# 2019_Dashboard.net
KiCad netlist of a schematic drawn in EAGLE
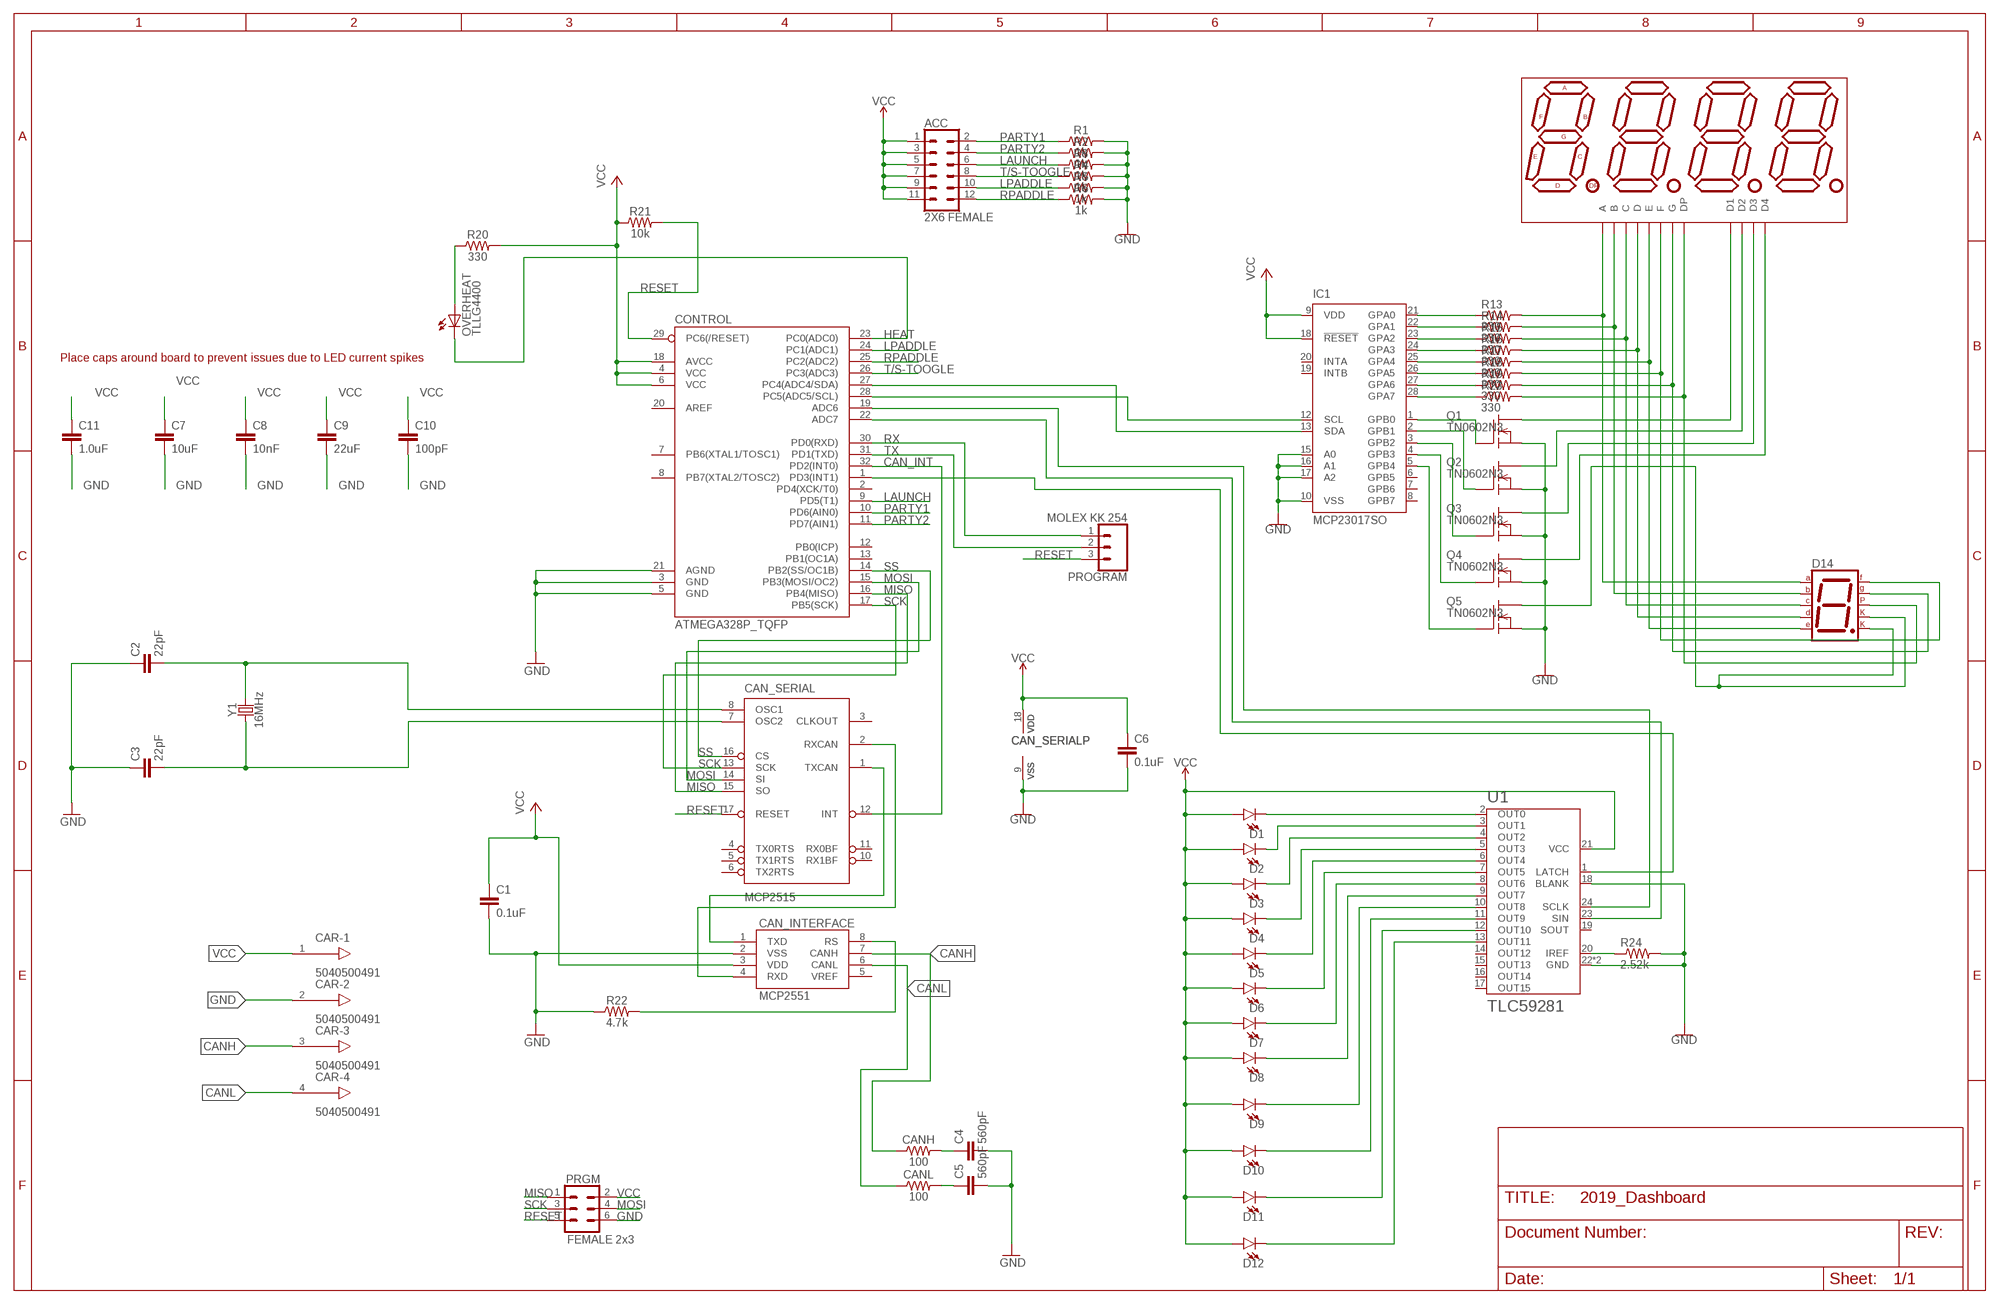
[diagram p0: schematic, sheet 1]

(export (version "E")
  (design (tool "Eeschema 10.0.6"))
  (components
    (comp (ref "ACC")
      (value "2X6 FEMALE")
      (footprint "eagle-import:2X6")
      (libsource (lib "eagle-import") (part "CONN_06X2PTH_FEMALE"))
    )
    (comp (ref "C1")
      (value "0.1uF")
      (footprint "eagle-import:0603")
      (libsource (lib "eagle-import") (part "0.1UF-0603-25V-(+80/-20%)"))
    )
    (comp (ref "C2")
      (value "22pF")
      (footprint "eagle-import:0603")
      (libsource (lib "eagle-import") (part "22PF-0603-50V-5%"))
    )
    (comp (ref "C3")
      (value "22pF")
      (footprint "eagle-import:0603")
      (libsource (lib "eagle-import") (part "22PF-0603-50V-5%"))
    )
    (comp (ref "C4")
      (value "560pF")
      (footprint "eagle-import:0603")
      (libsource (lib "eagle-import") (part "560PF-0603-50V-5%"))
    )
    (comp (ref "C5")
      (value "560pF")
      (footprint "eagle-import:0603")
      (libsource (lib "eagle-import") (part "560PF-0603-50V-5%"))
    )
    (comp (ref "C6")
      (value "0.1uF")
      (footprint "eagle-import:0402")
      (libsource (lib "eagle-import") (part "0.1UF-0402-16V-10%"))
    )
    (comp (ref "C7")
      (value "10uF")
      (footprint "eagle-import:0805")
      (libsource (lib "eagle-import") (part "10UF-0805-10V-10%"))
    )
    (comp (ref "C8")
      (value "10nF")
      (footprint "eagle-import:0603")
      (libsource (lib "eagle-import") (part "10NF-0603-50V-10%"))
    )
    (comp (ref "C9")
      (value "22uF")
      (footprint "eagle-import:0805")
      (libsource (lib "eagle-import") (part "22UF-0805-6.3V-20%"))
    )
    (comp (ref "C10")
      (value "100pF")
      (footprint "eagle-import:0603")
      (libsource (lib "eagle-import") (part "100PF-0603-50V-5%"))
    )
    (comp (ref "C11")
      (value "1.0uF")
      (footprint "eagle-import:0805")
      (libsource (lib "eagle-import") (part "1.0UF-0805-25V-(+80/-20%)"))
    )
    (comp (ref "CANH")
      (value "100")
      (footprint "eagle-import:0603")
      (libsource (lib "eagle-import") (part "100OHM-0603-1/4W-5%"))
    )
    (comp (ref "CANL")
      (value "100")
      (footprint "eagle-import:0603")
      (libsource (lib "eagle-import") (part "100OHM-0603-1/4W-5%"))
    )
    (comp (ref "CAN_INTERFACE")
      (value "MCP2551")
      (footprint "eagle-import:SO08")
      (libsource (lib "eagle-import") (part "MCP2551"))
    )
    (comp (ref "CAN_SERIAL")
      (value "MCP2515")
      (footprint "eagle-import:SO18W")
      (libsource (lib "eagle-import") (part "MCP2515(MCP2510)SO"))
    )
    (comp (ref "CAR")
      (value "5040500491")
      (footprint "eagle-import:PICOLOCK505050-0491")
      (fields (field (name "MANUFACTURER") "Molex Inc"))
      (libsource (lib "eagle-import") (part "5040500491"))
    )
    (comp (ref "CONTROL")
      (value "ATMEGA328P_TQFP")
      (footprint "eagle-import:TQFP32-08")
      (libsource (lib "eagle-import") (part "ATMEGA328P_TQFP"))
    )
    (comp (ref "D1")
      (value "LED5MM")
      (footprint "eagle-import:LED_5MM")
      (libsource (lib "eagle-import") (part "LED5MM"))
    )
    (comp (ref "D2")
      (value "LED5MM")
      (footprint "eagle-import:LED_5MM")
      (libsource (lib "eagle-import") (part "LED5MM"))
    )
    (comp (ref "D3")
      (value "LED5MM")
      (footprint "eagle-import:LED_5MM")
      (libsource (lib "eagle-import") (part "LED5MM"))
    )
    (comp (ref "D4")
      (value "LED5MM")
      (footprint "eagle-import:LED_5MM")
      (libsource (lib "eagle-import") (part "LED5MM"))
    )
    (comp (ref "D5")
      (value "LED5MM")
      (footprint "eagle-import:LED_5MM")
      (libsource (lib "eagle-import") (part "LED5MM"))
    )
    (comp (ref "D6")
      (value "LED5MM")
      (footprint "eagle-import:LED_5MM")
      (libsource (lib "eagle-import") (part "LED5MM"))
    )
    (comp (ref "D7")
      (value "LED5MM")
      (footprint "eagle-import:LED_5MM")
      (libsource (lib "eagle-import") (part "LED5MM"))
    )
    (comp (ref "D8")
      (value "LED5MM")
      (footprint "eagle-import:LED_5MM")
      (libsource (lib "eagle-import") (part "LED5MM"))
    )
    (comp (ref "D9")
      (value "LED5MM")
      (footprint "eagle-import:LED_5MM")
      (libsource (lib "eagle-import") (part "LED5MM"))
    )
    (comp (ref "D10")
      (value "LED5MM")
      (footprint "eagle-import:LED_5MM")
      (libsource (lib "eagle-import") (part "LED5MM"))
    )
    (comp (ref "D11")
      (value "LED5MM")
      (footprint "eagle-import:LED_5MM")
      (libsource (lib "eagle-import") (part "LED5MM"))
    )
    (comp (ref "D12")
      (value "LED5MM")
      (footprint "eagle-import:LED_5MM")
      (libsource (lib "eagle-import") (part "LED5MM"))
    )
    (comp (ref "D14")
      (value "7SEG-CK")
      (footprint "eagle-import:7SEG-13")
      (libsource (lib "eagle-import") (part "7SEG-CK"))
    )
    (comp (ref "DISP1")
      (value "ATA8041ARBJ")
      (footprint "eagle-import:7-SEGMENT-4DIGIT-20MM")
      (libsource (lib "eagle-import") (part "7-SEGMENT-4DIGIT-20MM-RED"))
    )
    (comp (ref "IC1")
      (value "MCP23017SO")
      (footprint "eagle-import:SO28W")
      (libsource (lib "eagle-import") (part "MCP23017SO"))
    )
    (comp (ref "OVERHEAT")
      (value "TLLG4400")
      (footprint "eagle-import:LED3MM")
      (fields (field (name "MF") "VISHAY SEMICONDUCTOR"))
      (libsource (lib "eagle-import") (part "TLLG4400"))
    )
    (comp (ref "PRGM")
      (value "FEMALE 2x3")
      (footprint "eagle-import:2X3")
      (libsource (lib "eagle-import") (part "CONN_03X2FEMALE"))
    )
    (comp (ref "PROGRAM")
      (value "MOLEX KK 254")
      (footprint "eagle-import:1X03")
      (libsource (lib "eagle-import") (part "CONN_03"))
    )
    (comp (ref "Q1")
      (value "TN0602N3")
      (footprint "eagle-import:TO-92")
      (libsource (lib "eagle-import") (part "TN0602N3"))
    )
    (comp (ref "Q2")
      (value "TN0602N3")
      (footprint "eagle-import:TO-92")
      (libsource (lib "eagle-import") (part "TN0602N3"))
    )
    (comp (ref "Q3")
      (value "TN0602N3")
      (footprint "eagle-import:TO-92")
      (libsource (lib "eagle-import") (part "TN0602N3"))
    )
    (comp (ref "Q4")
      (value "TN0602N3")
      (footprint "eagle-import:TO-92")
      (libsource (lib "eagle-import") (part "TN0602N3"))
    )
    (comp (ref "Q5")
      (value "TN0602N3")
      (footprint "eagle-import:TO-92")
      (libsource (lib "eagle-import") (part "TN0602N3"))
    )
    (comp (ref "R1")
      (value "1k")
      (footprint "eagle-import:0603")
      (libsource (lib "eagle-import") (part "1KOHM-0603-1/10W-1%"))
    )
    (comp (ref "R2")
      (value "1k")
      (footprint "eagle-import:0603")
      (libsource (lib "eagle-import") (part "1KOHM-0603-1/10W-1%"))
    )
    (comp (ref "R3")
      (value "1k")
      (footprint "eagle-import:0603")
      (libsource (lib "eagle-import") (part "1KOHM-0603-1/10W-1%"))
    )
    (comp (ref "R4")
      (value "1k")
      (footprint "eagle-import:0603")
      (libsource (lib "eagle-import") (part "1KOHM-0603-1/10W-1%"))
    )
    (comp (ref "R5")
      (value "1k")
      (footprint "eagle-import:0603")
      (libsource (lib "eagle-import") (part "1KOHM-0603-1/10W-1%"))
    )
    (comp (ref "R6")
      (value "1k")
      (footprint "eagle-import:0603")
      (libsource (lib "eagle-import") (part "1KOHM-0603-1/10W-1%"))
    )
    (comp (ref "R13")
      (value "330")
      (footprint "eagle-import:R0603")
      (libsource (lib "eagle-import") (part "R-US_R0603"))
    )
    (comp (ref "R14")
      (value "330")
      (footprint "eagle-import:R0603")
      (libsource (lib "eagle-import") (part "R-US_R0603"))
    )
    (comp (ref "R15")
      (value "330")
      (footprint "eagle-import:R0603")
      (libsource (lib "eagle-import") (part "R-US_R0603"))
    )
    (comp (ref "R16")
      (value "330")
      (footprint "eagle-import:R0603")
      (libsource (lib "eagle-import") (part "R-US_R0603"))
    )
    (comp (ref "R17")
      (value "330")
      (footprint "eagle-import:R0603")
      (libsource (lib "eagle-import") (part "R-US_R0603"))
    )
    (comp (ref "R18")
      (value "330")
      (footprint "eagle-import:R0603")
      (libsource (lib "eagle-import") (part "R-US_R0603"))
    )
    (comp (ref "R19")
      (value "330")
      (footprint "eagle-import:R0603")
      (libsource (lib "eagle-import") (part "R-US_R0603"))
    )
    (comp (ref "R20")
      (value "330")
      (footprint "eagle-import:0603")
      (libsource (lib "eagle-import") (part "330OHM-0603-1/10W-1%"))
    )
    (comp (ref "R21")
      (value "10k")
      (footprint "eagle-import:0603")
      (libsource (lib "eagle-import") (part "10KOHM-0603-1/10W-1%"))
    )
    (comp (ref "R22")
      (value "4.7k")
      (footprint "eagle-import:0603")
      (libsource (lib "eagle-import") (part "4.7KOHM-0603-1/10W-1%"))
    )
    (comp (ref "R23")
      (value "330")
      (footprint "eagle-import:R0603")
      (libsource (lib "eagle-import") (part "R-US_R0603"))
    )
    (comp (ref "R24")
      (value "2.52k")
      (footprint "eagle-import:R0603")
      (libsource (lib "eagle-import") (part "R-US_R0603"))
    )
    (comp (ref "U1")
      (value "TLC59281")
      (footprint "eagle-import:QFN-24")
      (fields (field (name "MF") "Texas Instruments"))
      (libsource (lib "eagle-import") (part "TLC59281"))
    )
    (comp (ref "Y1")
      (value "16MHz")
      (footprint "eagle-import:HC49US")
      (libsource (lib "eagle-import") (part "CRYSTAL-16MHZPTH-HC49US"))
    )
  )
  (nets
    (net (code "1") (name "/CAN_INT") (class "Default")
      (node (ref "CAN_SERIAL") (pin "12") (pinfunction "INT_12") (pintype "output"))
      (node (ref "CONTROL") (pin "32") (pinfunction "PD2(INT0)_32") (pintype "bidirectional"))
    )
    (net (code "2") (name "/HEAT") (class "Default")
      (node (ref "CONTROL") (pin "23") (pinfunction "PC0(ADC0)_23") (pintype "bidirectional"))
      (node (ref "OVERHEAT") (pin "K") (pinfunction "C_K") (pintype "passive"))
    )
    (net (code "3") (name "/LAUNCH") (class "Default")
      (node (ref "ACC") (pin "6") (pinfunction "6_6") (pintype "passive"))
      (node (ref "CONTROL") (pin "9") (pinfunction "PD5(T1)_9") (pintype "bidirectional"))
      (node (ref "R3") (pin "1") (pinfunction "1_1") (pintype "passive"))
    )
    (net (code "4") (name "/LPADDLE") (class "Default")
      (node (ref "ACC") (pin "10") (pinfunction "10_10") (pintype "passive"))
      (node (ref "CONTROL") (pin "24") (pinfunction "PC1(ADC1)_24") (pintype "bidirectional"))
      (node (ref "R5") (pin "1") (pinfunction "1_1") (pintype "passive"))
    )
    (net (code "5") (name "/MISO") (class "Default")
      (node (ref "CAN_SERIAL") (pin "15") (pinfunction "SO_15") (pintype "output"))
      (node (ref "CONTROL") (pin "16") (pinfunction "PB4(MISO)_16") (pintype "bidirectional"))
      (node (ref "PRGM") (pin "1") (pinfunction "1_1") (pintype "bidirectional"))
    )
    (net (code "6") (name "/MOSI") (class "Default")
      (node (ref "CAN_SERIAL") (pin "14") (pinfunction "SI_14") (pintype "input"))
      (node (ref "CONTROL") (pin "15") (pinfunction "PB3(MOSI/OC2)_15") (pintype "bidirectional"))
      (node (ref "PRGM") (pin "4") (pinfunction "4_4") (pintype "bidirectional"))
    )
    (net (code "7") (name "/PARTY1") (class "Default")
      (node (ref "ACC") (pin "2") (pinfunction "2_2") (pintype "passive"))
      (node (ref "CONTROL") (pin "10") (pinfunction "PD6(AIN0)_10") (pintype "bidirectional"))
      (node (ref "R1") (pin "1") (pinfunction "1_1") (pintype "passive"))
    )
    (net (code "8") (name "/PARTY2") (class "Default")
      (node (ref "ACC") (pin "4") (pinfunction "4_4") (pintype "passive"))
      (node (ref "CONTROL") (pin "11") (pinfunction "PD7(AIN1)_11") (pintype "bidirectional"))
      (node (ref "R2") (pin "1") (pinfunction "1_1") (pintype "passive"))
    )
    (net (code "9") (name "/RESET") (class "Default")
      (node (ref "CAN_SERIAL") (pin "17") (pinfunction "RESET_17") (pintype "input"))
      (node (ref "CONTROL") (pin "29") (pinfunction "PC6(/RESET)_29") (pintype "bidirectional"))
      (node (ref "PRGM") (pin "5") (pinfunction "5_5") (pintype "bidirectional"))
      (node (ref "PROGRAM") (pin "3") (pinfunction "3_3") (pintype "passive"))
      (node (ref "R21") (pin "2") (pinfunction "2_2") (pintype "passive"))
    )
    (net (code "10") (name "/RPADDLE") (class "Default")
      (node (ref "ACC") (pin "12") (pinfunction "12_12") (pintype "passive"))
      (node (ref "CONTROL") (pin "25") (pinfunction "PC2(ADC2)_25") (pintype "bidirectional"))
      (node (ref "R6") (pin "1") (pinfunction "1_1") (pintype "passive"))
    )
    (net (code "11") (name "/RX") (class "Default")
      (node (ref "CONTROL") (pin "30") (pinfunction "PD0(RXD)_30") (pintype "bidirectional"))
      (node (ref "PROGRAM") (pin "1") (pinfunction "1_1") (pintype "passive"))
    )
    (net (code "12") (name "/SCK") (class "Default")
      (node (ref "CAN_SERIAL") (pin "13") (pinfunction "SCK_13") (pintype "input"))
      (node (ref "CONTROL") (pin "17") (pinfunction "PB5(SCK)_17") (pintype "bidirectional"))
      (node (ref "PRGM") (pin "3") (pinfunction "3_3") (pintype "bidirectional"))
    )
    (net (code "13") (name "/SS") (class "Default")
      (node (ref "CAN_SERIAL") (pin "16") (pinfunction "CS_16") (pintype "input"))
      (node (ref "CONTROL") (pin "14") (pinfunction "PB2(SS/OC1B)_14") (pintype "bidirectional"))
    )
    (net (code "14") (name "/TX") (class "Default")
      (node (ref "CONTROL") (pin "31") (pinfunction "PD1(TXD)_31") (pintype "bidirectional"))
      (node (ref "PROGRAM") (pin "2") (pinfunction "2_2") (pintype "passive"))
    )
    (net (code "15") (name "/T{slash}S-TOOGLE") (class "Default")
      (node (ref "ACC") (pin "8") (pinfunction "8_8") (pintype "passive"))
      (node (ref "CONTROL") (pin "26") (pinfunction "PC3(ADC3)_26") (pintype "bidirectional"))
      (node (ref "R4") (pin "1") (pinfunction "1_1") (pintype "passive"))
    )
    (net (code "16") (name "CANH") (class "Default")
      (node (ref "CANH") (pin "1") (pinfunction "1_1") (pintype "passive"))
      (node (ref "CAN_INTERFACE") (pin "7") (pinfunction "CANH_7") (pintype "bidirectional"))
      (node (ref "CAR") (pin "3") (pinfunction "P$1_3") (pintype "bidirectional"))
    )
    (net (code "17") (name "CANL") (class "Default")
      (node (ref "CANL") (pin "1") (pinfunction "1_1") (pintype "passive"))
      (node (ref "CAN_INTERFACE") (pin "6") (pinfunction "CANL_6") (pintype "bidirectional"))
      (node (ref "CAR") (pin "4") (pinfunction "P$1_4") (pintype "bidirectional"))
    )
    (net (code "18") (name "GND") (class "Default")
      (node (ref "C1") (pin "2") (pinfunction "2_2") (pintype "passive"))
      (node (ref "C10") (pin "2") (pinfunction "2_2") (pintype "passive"))
      (node (ref "C11") (pin "2") (pinfunction "2_2") (pintype "passive"))
      (node (ref "C2") (pin "1") (pinfunction "1_1") (pintype "passive"))
      (node (ref "C3") (pin "1") (pinfunction "1_1") (pintype "passive"))
      (node (ref "C4") (pin "2") (pinfunction "2_2") (pintype "passive"))
      (node (ref "C5") (pin "2") (pinfunction "2_2") (pintype "passive"))
      (node (ref "C6") (pin "2") (pinfunction "2_2") (pintype "passive"))
      (node (ref "C7") (pin "2") (pinfunction "2_2") (pintype "passive"))
      (node (ref "C8") (pin "2") (pinfunction "2_2") (pintype "passive"))
      (node (ref "C9") (pin "2") (pinfunction "2_2") (pintype "passive"))
      (node (ref "CAN_INTERFACE") (pin "2") (pinfunction "VSS_2") (pintype "bidirectional"))
      (node (ref "CAN_SERIAL") (pin "9") (pinfunction "VSS_9") (pintype "power_in"))
      (node (ref "CAR") (pin "2") (pinfunction "P$1_2") (pintype "bidirectional"))
      (node (ref "CONTROL") (pin "21") (pinfunction "AGND_21") (pintype "bidirectional"))
      (node (ref "CONTROL") (pin "3") (pinfunction "GND_3") (pintype "bidirectional"))
      (node (ref "CONTROL") (pin "5") (pinfunction "GND_5") (pintype "bidirectional"))
      (node (ref "IC1") (pin "10") (pinfunction "VSS_10") (pintype "power_in"))
      (node (ref "IC1") (pin "15") (pinfunction "A0_15") (pintype "input"))
      (node (ref "IC1") (pin "16") (pinfunction "A1_16") (pintype "input"))
      (node (ref "IC1") (pin "17") (pinfunction "A2_17") (pintype "input"))
      (node (ref "PRGM") (pin "6") (pinfunction "6_6") (pintype "bidirectional"))
      (node (ref "Q1") (pin "1") (pinfunction "S_1") (pintype "passive"))
      (node (ref "Q2") (pin "1") (pinfunction "S_1") (pintype "passive"))
      (node (ref "Q3") (pin "1") (pinfunction "S_1") (pintype "passive"))
      (node (ref "Q4") (pin "1") (pinfunction "S_1") (pintype "passive"))
      (node (ref "Q5") (pin "1") (pinfunction "S_1") (pintype "passive"))
      (node (ref "R1") (pin "2") (pinfunction "2_2") (pintype "passive"))
      (node (ref "R2") (pin "2") (pinfunction "2_2") (pintype "passive"))
      (node (ref "R22") (pin "1") (pinfunction "1_1") (pintype "passive"))
      (node (ref "R24") (pin "2") (pinfunction "2_2") (pintype "passive"))
      (node (ref "R3") (pin "2") (pinfunction "2_2") (pintype "passive"))
      (node (ref "R4") (pin "2") (pinfunction "2_2") (pintype "passive"))
      (node (ref "R5") (pin "2") (pinfunction "2_2") (pintype "passive"))
      (node (ref "R6") (pin "2") (pinfunction "2_2") (pintype "passive"))
      (node (ref "U1") (pin "18") (pinfunction "BLANK_18") (pintype "bidirectional"))
      (node (ref "U1") (pin "22") (pinfunction "GND_22") (pintype "bidirectional"))
      (node (ref "U1") (pin "EP") (pinfunction "GND_EP") (pintype "bidirectional"))
    )
    (net (code "19") (name "Net-(C4-Pad1)") (class "Default")
      (node (ref "C4") (pin "1") (pinfunction "1_1") (pintype "passive"))
      (node (ref "CANH") (pin "2") (pinfunction "2_2") (pintype "passive"))
    )
    (net (code "20") (name "Net-(C5-Pad1)") (class "Default")
      (node (ref "C5") (pin "1") (pinfunction "1_1") (pintype "passive"))
      (node (ref "CANL") (pin "2") (pinfunction "2_2") (pintype "passive"))
    )
    (net (code "21") (name "Net-(CAN_INTERFACE-RS)") (class "Default")
      (node (ref "CAN_INTERFACE") (pin "8") (pinfunction "RS_8") (pintype "bidirectional"))
      (node (ref "R22") (pin "2") (pinfunction "2_2") (pintype "passive"))
    )
    (net (code "22") (name "Net-(CAN_INTERFACE-RXD)") (class "Default")
      (node (ref "CAN_INTERFACE") (pin "4") (pinfunction "RXD_4") (pintype "bidirectional"))
      (node (ref "CAN_SERIAL") (pin "2") (pinfunction "RXCAN_2") (pintype "input"))
    )
    (net (code "23") (name "Net-(CAN_INTERFACE-TXD)") (class "Default")
      (node (ref "CAN_INTERFACE") (pin "1") (pinfunction "TXD_1") (pintype "bidirectional"))
      (node (ref "CAN_SERIAL") (pin "1") (pinfunction "TXCAN_1") (pintype "output"))
    )
    (net (code "24") (name "Net-(CAN_SERIALA-OSC1)") (class "Default")
      (node (ref "C2") (pin "2") (pinfunction "2_2") (pintype "passive"))
      (node (ref "CAN_SERIAL") (pin "8") (pinfunction "OSC1_8") (pintype "input"))
      (node (ref "Y1") (pin "2") (pinfunction "2_2") (pintype "passive"))
    )
    (net (code "25") (name "Net-(CAN_SERIALA-OSC2)") (class "Default")
      (node (ref "C3") (pin "2") (pinfunction "2_2") (pintype "passive"))
      (node (ref "CAN_SERIAL") (pin "7") (pinfunction "OSC2_7") (pintype "output"))
      (node (ref "Y1") (pin "1") (pinfunction "1_1") (pintype "passive"))
    )
    (net (code "26") (name "Net-(CONTROL-ADC6)") (class "Default")
      (node (ref "CONTROL") (pin "19") (pinfunction "ADC6_19") (pintype "bidirectional"))
      (node (ref "U1") (pin "24") (pinfunction "SCLK_24") (pintype "bidirectional"))
    )
    (net (code "27") (name "Net-(CONTROL-ADC7)") (class "Default")
      (node (ref "CONTROL") (pin "22") (pinfunction "ADC7_22") (pintype "bidirectional"))
      (node (ref "U1") (pin "23") (pinfunction "SIN_23") (pintype "bidirectional"))
    )
    (net (code "28") (name "Net-(CONTROL-PC4(ADC4{slash}SDA))") (class "Default")
      (node (ref "CONTROL") (pin "27") (pinfunction "PC4(ADC4/SDA)_27") (pintype "bidirectional"))
      (node (ref "IC1") (pin "13") (pinfunction "SDA_13") (pintype "bidirectional"))
    )
    (net (code "29") (name "Net-(CONTROL-PC5(ADC5{slash}SCL))") (class "Default")
      (node (ref "CONTROL") (pin "28") (pinfunction "PC5(ADC5/SCL)_28") (pintype "bidirectional"))
      (node (ref "IC1") (pin "12") (pinfunction "SCL_12") (pintype "input"))
    )
    (net (code "30") (name "Net-(CONTROL-PD3(INT1))") (class "Default")
      (node (ref "CONTROL") (pin "1") (pinfunction "PD3(INT1)_1") (pintype "bidirectional"))
      (node (ref "U1") (pin "1") (pinfunction "LATCH_1") (pintype "bidirectional"))
    )
    (net (code "31") (name "Net-(D1-C)") (class "Default")
      (node (ref "D1") (pin "K") (pinfunction "C_K") (pintype "passive"))
      (node (ref "U1") (pin "2") (pinfunction "OUT0_2") (pintype "bidirectional"))
    )
    (net (code "32") (name "Net-(D2-C)") (class "Default")
      (node (ref "D2") (pin "K") (pinfunction "C_K") (pintype "passive"))
      (node (ref "U1") (pin "3") (pinfunction "OUT1_3") (pintype "bidirectional"))
    )
    (net (code "33") (name "Net-(D3-C)") (class "Default")
      (node (ref "D3") (pin "K") (pinfunction "C_K") (pintype "passive"))
      (node (ref "U1") (pin "4") (pinfunction "OUT2_4") (pintype "bidirectional"))
    )
    (net (code "34") (name "Net-(D4-C)") (class "Default")
      (node (ref "D4") (pin "K") (pinfunction "C_K") (pintype "passive"))
      (node (ref "U1") (pin "5") (pinfunction "OUT3_5") (pintype "bidirectional"))
    )
    (net (code "35") (name "Net-(D5-C)") (class "Default")
      (node (ref "D5") (pin "K") (pinfunction "C_K") (pintype "passive"))
      (node (ref "U1") (pin "6") (pinfunction "OUT4_6") (pintype "bidirectional"))
    )
    (net (code "36") (name "Net-(D6-C)") (class "Default")
      (node (ref "D6") (pin "K") (pinfunction "C_K") (pintype "passive"))
      (node (ref "U1") (pin "7") (pinfunction "OUT5_7") (pintype "bidirectional"))
    )
    (net (code "37") (name "Net-(D7-C)") (class "Default")
      (node (ref "D7") (pin "K") (pinfunction "C_K") (pintype "passive"))
      (node (ref "U1") (pin "8") (pinfunction "OUT6_8") (pintype "bidirectional"))
    )
    (net (code "38") (name "Net-(D8-C)") (class "Default")
      (node (ref "D8") (pin "K") (pinfunction "C_K") (pintype "passive"))
      (node (ref "U1") (pin "9") (pinfunction "OUT7_9") (pintype "bidirectional"))
    )
    (net (code "39") (name "Net-(D9-C)") (class "Default")
      (node (ref "D9") (pin "K") (pinfunction "C_K") (pintype "passive"))
      (node (ref "U1") (pin "10") (pinfunction "OUT8_10") (pintype "bidirectional"))
    )
    (net (code "40") (name "Net-(D10-C)") (class "Default")
      (node (ref "D10") (pin "K") (pinfunction "C_K") (pintype "passive"))
      (node (ref "U1") (pin "11") (pinfunction "OUT9_11") (pintype "bidirectional"))
    )
    (net (code "41") (name "Net-(D11-C)") (class "Default")
      (node (ref "D11") (pin "K") (pinfunction "C_K") (pintype "passive"))
      (node (ref "U1") (pin "12") (pinfunction "OUT10_12") (pintype "bidirectional"))
    )
    (net (code "42") (name "Net-(D12-C)") (class "Default")
      (node (ref "D12") (pin "K") (pinfunction "C_K") (pintype "passive"))
      (node (ref "U1") (pin "13") (pinfunction "OUT11_13") (pintype "bidirectional"))
    )
    (net (code "43") (name "Net-(D14-A)") (class "Default")
      (node (ref "D14") (pin "7") (pinfunction "A_7") (pintype "passive"))
      (node (ref "DISP1") (pin "11") (pinfunction "A_11") (pintype "bidirectional"))
      (node (ref "R13") (pin "2") (pinfunction "2_2") (pintype "passive"))
    )
    (net (code "44") (name "Net-(D14-B)") (class "Default")
      (node (ref "D14") (pin "6") (pinfunction "B_6") (pintype "passive"))
      (node (ref "DISP1") (pin "7") (pinfunction "B_7") (pintype "bidirectional"))
      (node (ref "R14") (pin "2") (pinfunction "2_2") (pintype "passive"))
    )
    (net (code "45") (name "Net-(D14-C)") (class "Default")
      (node (ref "D14") (pin "4") (pinfunction "C_4") (pintype "passive"))
      (node (ref "DISP1") (pin "4") (pinfunction "C_4") (pintype "bidirectional"))
      (node (ref "R15") (pin "2") (pinfunction "2_2") (pintype "passive"))
    )
    (net (code "46") (name "Net-(D14-CK1)") (class "Default")
      (node (ref "D14") (pin "3") (pinfunction "CK1_3") (pintype "passive"))
      (node (ref "D14") (pin "8") (pinfunction "CK2_8") (pintype "passive"))
      (node (ref "Q5") (pin "3") (pinfunction "D_3") (pintype "passive"))
    )
    (net (code "47") (name "Net-(D14-D)") (class "Default")
      (node (ref "D14") (pin "2") (pinfunction "D_2") (pintype "passive"))
      (node (ref "DISP1") (pin "2") (pinfunction "D_2") (pintype "bidirectional"))
      (node (ref "R16") (pin "2") (pinfunction "2_2") (pintype "passive"))
    )
    (net (code "48") (name "Net-(D14-DP)") (class "Default")
      (node (ref "D14") (pin "5") (pinfunction "DP_5") (pintype "passive"))
      (node (ref "DISP1") (pin "3") (pinfunction "DP_3") (pintype "bidirectional"))
      (node (ref "R23") (pin "2") (pinfunction "2_2") (pintype "passive"))
    )
    (net (code "49") (name "Net-(D14-E)") (class "Default")
      (node (ref "D14") (pin "1") (pinfunction "E_1") (pintype "passive"))
      (node (ref "DISP1") (pin "1") (pinfunction "E_1") (pintype "bidirectional"))
      (node (ref "R17") (pin "2") (pinfunction "2_2") (pintype "passive"))
    )
    (net (code "50") (name "Net-(D14-F)") (class "Default")
      (node (ref "D14") (pin "9") (pinfunction "F_9") (pintype "passive"))
      (node (ref "DISP1") (pin "10") (pinfunction "F_10") (pintype "bidirectional"))
      (node (ref "R18") (pin "2") (pinfunction "2_2") (pintype "passive"))
    )
    (net (code "51") (name "Net-(D14-G)") (class "Default")
      (node (ref "D14") (pin "10") (pinfunction "G_10") (pintype "passive"))
      (node (ref "DISP1") (pin "5") (pinfunction "G_5") (pintype "bidirectional"))
      (node (ref "R19") (pin "2") (pinfunction "2_2") (pintype "passive"))
    )
    (net (code "52") (name "Net-(DISP1-D1)") (class "Default")
      (node (ref "DISP1") (pin "12") (pinfunction "D1_12") (pintype "bidirectional"))
      (node (ref "Q1") (pin "3") (pinfunction "D_3") (pintype "passive"))
    )
    (net (code "53") (name "Net-(DISP1-D2)") (class "Default")
      (node (ref "DISP1") (pin "9") (pinfunction "D2_9") (pintype "bidirectional"))
      (node (ref "Q2") (pin "3") (pinfunction "D_3") (pintype "passive"))
    )
    (net (code "54") (name "Net-(DISP1-D3)") (class "Default")
      (node (ref "DISP1") (pin "8") (pinfunction "D3_8") (pintype "bidirectional"))
      (node (ref "Q3") (pin "3") (pinfunction "D_3") (pintype "passive"))
    )
    (net (code "55") (name "Net-(DISP1-D4)") (class "Default")
      (node (ref "DISP1") (pin "6") (pinfunction "D4_6") (pintype "bidirectional"))
      (node (ref "Q4") (pin "3") (pinfunction "D_3") (pintype "passive"))
    )
    (net (code "56") (name "Net-(IC1-GPA0)") (class "Default")
      (node (ref "IC1") (pin "21") (pinfunction "GPA0_21") (pintype "bidirectional"))
      (node (ref "R13") (pin "1") (pinfunction "1_1") (pintype "passive"))
    )
    (net (code "57") (name "Net-(IC1-GPA1)") (class "Default")
      (node (ref "IC1") (pin "22") (pinfunction "GPA1_22") (pintype "bidirectional"))
      (node (ref "R14") (pin "1") (pinfunction "1_1") (pintype "passive"))
    )
    (net (code "58") (name "Net-(IC1-GPA2)") (class "Default")
      (node (ref "IC1") (pin "23") (pinfunction "GPA2_23") (pintype "bidirectional"))
      (node (ref "R15") (pin "1") (pinfunction "1_1") (pintype "passive"))
    )
    (net (code "59") (name "Net-(IC1-GPA3)") (class "Default")
      (node (ref "IC1") (pin "24") (pinfunction "GPA3_24") (pintype "bidirectional"))
      (node (ref "R16") (pin "1") (pinfunction "1_1") (pintype "passive"))
    )
    (net (code "60") (name "Net-(IC1-GPA4)") (class "Default")
      (node (ref "IC1") (pin "25") (pinfunction "GPA4_25") (pintype "bidirectional"))
      (node (ref "R17") (pin "1") (pinfunction "1_1") (pintype "passive"))
    )
    (net (code "61") (name "Net-(IC1-GPA5)") (class "Default")
      (node (ref "IC1") (pin "26") (pinfunction "GPA5_26") (pintype "bidirectional"))
      (node (ref "R18") (pin "1") (pinfunction "1_1") (pintype "passive"))
    )
    (net (code "62") (name "Net-(IC1-GPA6)") (class "Default")
      (node (ref "IC1") (pin "27") (pinfunction "GPA6_27") (pintype "bidirectional"))
      (node (ref "R19") (pin "1") (pinfunction "1_1") (pintype "passive"))
    )
    (net (code "63") (name "Net-(IC1-GPA7)") (class "Default")
      (node (ref "IC1") (pin "28") (pinfunction "GPA7_28") (pintype "bidirectional"))
      (node (ref "R23") (pin "1") (pinfunction "1_1") (pintype "passive"))
    )
    (net (code "64") (name "Net-(IC1-GPB0)") (class "Default")
      (node (ref "IC1") (pin "1") (pinfunction "GPB0_1") (pintype "bidirectional"))
      (node (ref "Q1") (pin "2") (pinfunction "G_2") (pintype "passive"))
    )
    (net (code "65") (name "Net-(IC1-GPB1)") (class "Default")
      (node (ref "IC1") (pin "2") (pinfunction "GPB1_2") (pintype "bidirectional"))
      (node (ref "Q2") (pin "2") (pinfunction "G_2") (pintype "passive"))
    )
    (net (code "66") (name "Net-(IC1-GPB2)") (class "Default")
      (node (ref "IC1") (pin "3") (pinfunction "GPB2_3") (pintype "bidirectional"))
      (node (ref "Q3") (pin "2") (pinfunction "G_2") (pintype "passive"))
    )
    (net (code "67") (name "Net-(IC1-GPB3)") (class "Default")
      (node (ref "IC1") (pin "4") (pinfunction "GPB3_4") (pintype "bidirectional"))
      (node (ref "Q4") (pin "2") (pinfunction "G_2") (pintype "passive"))
    )
    (net (code "68") (name "Net-(IC1-GPB4)") (class "Default")
      (node (ref "IC1") (pin "5") (pinfunction "GPB4_5") (pintype "bidirectional"))
      (node (ref "Q5") (pin "2") (pinfunction "G_2") (pintype "passive"))
    )
    (net (code "69") (name "Net-(OVERHEAT-PadA)") (class "Default")
      (node (ref "OVERHEAT") (pin "A") (pinfunction "A_A") (pintype "passive"))
      (node (ref "R20") (pin "1") (pinfunction "1_1") (pintype "passive"))
    )
    (net (code "70") (name "Net-(U1-IREF)") (class "Default")
      (node (ref "R24") (pin "1") (pinfunction "1_1") (pintype "passive"))
      (node (ref "U1") (pin "20") (pinfunction "IREF_20") (pintype "bidirectional"))
    )
    (net (code "71") (name "VCC") (class "Default")
      (node (ref "ACC") (pin "1") (pinfunction "1_1") (pintype "passive"))
      (node (ref "ACC") (pin "11") (pinfunction "11_11") (pintype "passive"))
      (node (ref "ACC") (pin "3") (pinfunction "3_3") (pintype "passive"))
      (node (ref "ACC") (pin "5") (pinfunction "5_5") (pintype "passive"))
      (node (ref "ACC") (pin "7") (pinfunction "7_7") (pintype "passive"))
      (node (ref "ACC") (pin "9") (pinfunction "9_9") (pintype "passive"))
      (node (ref "C1") (pin "1") (pinfunction "1_1") (pintype "passive"))
      (node (ref "C10") (pin "1") (pinfunction "1_1") (pintype "passive"))
      (node (ref "C11") (pin "1") (pinfunction "1_1") (pintype "passive"))
      (node (ref "C6") (pin "1") (pinfunction "1_1") (pintype "passive"))
      (node (ref "C7") (pin "1") (pinfunction "1_1") (pintype "passive"))
      (node (ref "C8") (pin "1") (pinfunction "1_1") (pintype "passive"))
      (node (ref "C9") (pin "1") (pinfunction "1_1") (pintype "passive"))
      (node (ref "CAN_INTERFACE") (pin "3") (pinfunction "VDD_3") (pintype "bidirectional"))
      (node (ref "CAN_SERIAL") (pin "18") (pinfunction "VDD_18") (pintype "power_in"))
      (node (ref "CAR") (pin "1") (pinfunction "P$1_1") (pintype "bidirectional"))
      (node (ref "CONTROL") (pin "18") (pinfunction "AVCC_18") (pintype "bidirectional"))
      (node (ref "CONTROL") (pin "4") (pinfunction "VCC_4") (pintype "bidirectional"))
      (node (ref "CONTROL") (pin "6") (pinfunction "VCC_6") (pintype "bidirectional"))
      (node (ref "D1") (pin "A") (pinfunction "A_A") (pintype "passive"))
      (node (ref "D10") (pin "A") (pinfunction "A_A") (pintype "passive"))
      (node (ref "D11") (pin "A") (pinfunction "A_A") (pintype "passive"))
      (node (ref "D12") (pin "A") (pinfunction "A_A") (pintype "passive"))
      (node (ref "D2") (pin "A") (pinfunction "A_A") (pintype "passive"))
      (node (ref "D3") (pin "A") (pinfunction "A_A") (pintype "passive"))
      (node (ref "D4") (pin "A") (pinfunction "A_A") (pintype "passive"))
      (node (ref "D5") (pin "A") (pinfunction "A_A") (pintype "passive"))
      (node (ref "D6") (pin "A") (pinfunction "A_A") (pintype "passive"))
      (node (ref "D7") (pin "A") (pinfunction "A_A") (pintype "passive"))
      (node (ref "D8") (pin "A") (pinfunction "A_A") (pintype "passive"))
      (node (ref "D9") (pin "A") (pinfunction "A_A") (pintype "passive"))
      (node (ref "IC1") (pin "18") (pinfunction "~{RESET}_18") (pintype "input"))
      (node (ref "IC1") (pin "9") (pinfunction "VDD_9") (pintype "power_in"))
      (node (ref "PRGM") (pin "2") (pinfunction "2_2") (pintype "bidirectional"))
      (node (ref "R20") (pin "2") (pinfunction "2_2") (pintype "passive"))
      (node (ref "R21") (pin "1") (pinfunction "1_1") (pintype "passive"))
      (node (ref "U1") (pin "21") (pinfunction "VCC_21") (pintype "bidirectional"))
    )
    (net (code "72") (name "unconnected-(CAN_INTERFACE-VREF-Pad5)") (class "Default")
      (node (ref "CAN_INTERFACE") (pin "5") (pinfunction "VREF_5") (pintype "bidirectional"))
    )
    (net (code "73") (name "unconnected-(CAN_SERIALA-CLKOUT-Pad3)") (class "Default")
      (node (ref "CAN_SERIAL") (pin "3") (pinfunction "CLKOUT_3") (pintype "output"))
    )
    (net (code "74") (name "unconnected-(CAN_SERIALA-RX0BF-Pad11)") (class "Default")
      (node (ref "CAN_SERIAL") (pin "11") (pinfunction "RX0BF_11") (pintype "output"))
    )
    (net (code "75") (name "unconnected-(CAN_SERIALA-RX1BF-Pad10)") (class "Default")
      (node (ref "CAN_SERIAL") (pin "10") (pinfunction "RX1BF_10") (pintype "output"))
    )
    (net (code "76") (name "unconnected-(CAN_SERIALA-TX0RTS-Pad4)") (class "Default")
      (node (ref "CAN_SERIAL") (pin "4") (pinfunction "TX0RTS_4") (pintype "input"))
    )
    (net (code "77") (name "unconnected-(CAN_SERIALA-TX1RTS-Pad5)") (class "Default")
      (node (ref "CAN_SERIAL") (pin "5") (pinfunction "TX1RTS_5") (pintype "input"))
    )
    (net (code "78") (name "unconnected-(CAN_SERIALA-TX2RTS-Pad6)") (class "Default")
      (node (ref "CAN_SERIAL") (pin "6") (pinfunction "TX2RTS_6") (pintype "input"))
    )
    (net (code "79") (name "unconnected-(CONTROL-AREF-Pad20)") (class "Default")
      (node (ref "CONTROL") (pin "20") (pinfunction "AREF_20") (pintype "bidirectional"))
    )
    (net (code "80") (name "unconnected-(CONTROL-PB0(ICP)-Pad12)") (class "Default")
      (node (ref "CONTROL") (pin "12") (pinfunction "PB0(ICP)_12") (pintype "bidirectional"))
    )
    (net (code "81") (name "unconnected-(CONTROL-PB1(OC1A)-Pad13)") (class "Default")
      (node (ref "CONTROL") (pin "13") (pinfunction "PB1(OC1A)_13") (pintype "bidirectional"))
    )
    (net (code "82") (name "unconnected-(CONTROL-PB6(XTAL1{slash}TOSC1)-Pad7)") (class "Default")
      (node (ref "CONTROL") (pin "7") (pinfunction "PB6(XTAL1/TOSC1)_7") (pintype "bidirectional"))
    )
    (net (code "83") (name "unconnected-(CONTROL-PB7(XTAL2{slash}TOSC2)-Pad8)") (class "Default")
      (node (ref "CONTROL") (pin "8") (pinfunction "PB7(XTAL2/TOSC2)_8") (pintype "bidirectional"))
    )
    (net (code "84") (name "unconnected-(CONTROL-PD4(XCK{slash}T0)-Pad2)") (class "Default")
      (node (ref "CONTROL") (pin "2") (pinfunction "PD4(XCK/T0)_2") (pintype "bidirectional"))
    )
    (net (code "85") (name "unconnected-(IC1-GPB5-Pad6)") (class "Default")
      (node (ref "IC1") (pin "6") (pinfunction "GPB5_6") (pintype "bidirectional"))
    )
    (net (code "86") (name "unconnected-(IC1-GPB6-Pad7)") (class "Default")
      (node (ref "IC1") (pin "7") (pinfunction "GPB6_7") (pintype "bidirectional"))
    )
    (net (code "87") (name "unconnected-(IC1-GPB7-Pad8)") (class "Default")
      (node (ref "IC1") (pin "8") (pinfunction "GPB7_8") (pintype "bidirectional"))
    )
    (net (code "88") (name "unconnected-(IC1-INTA-Pad20)") (class "Default")
      (node (ref "IC1") (pin "20") (pinfunction "INTA_20") (pintype "output"))
    )
    (net (code "89") (name "unconnected-(IC1-INTB-Pad19)") (class "Default")
      (node (ref "IC1") (pin "19") (pinfunction "INTB_19") (pintype "output"))
    )
    (net (code "90") (name "unconnected-(U1-OUT12-Pad14)") (class "Default")
      (node (ref "U1") (pin "14") (pinfunction "OUT12_14") (pintype "bidirectional"))
    )
    (net (code "91") (name "unconnected-(U1-OUT13-Pad15)") (class "Default")
      (node (ref "U1") (pin "15") (pinfunction "OUT13_15") (pintype "bidirectional"))
    )
    (net (code "92") (name "unconnected-(U1-OUT14-Pad16)") (class "Default")
      (node (ref "U1") (pin "16") (pinfunction "OUT14_16") (pintype "bidirectional"))
    )
    (net (code "93") (name "unconnected-(U1-OUT15-Pad17)") (class "Default")
      (node (ref "U1") (pin "17") (pinfunction "OUT15_17") (pintype "bidirectional"))
    )
    (net (code "94") (name "unconnected-(U1-SOUT-Pad19)") (class "Default")
      (node (ref "U1") (pin "19") (pinfunction "SOUT_19") (pintype "bidirectional"))
    )
  )
)
